# nRF24L01_Shield.net
KiCad netlist of a schematic drawn in EAGLE
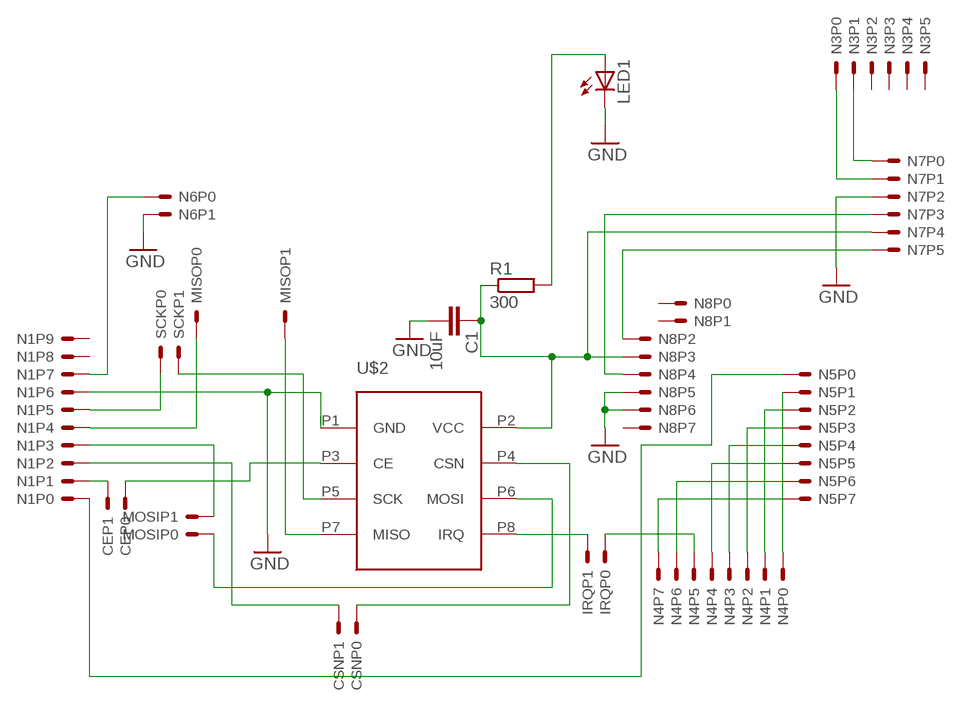
[diagram p0: schematic, sheet 1]

(export (version "E")
  (design (tool "Eeschema 10.0.6"))
  (components
    (comp (ref "C1")
      (value "10uF")
      (footprint "eagle-import:C2.5-4")
      (libsource (lib "eagle-import") (part "C2.5/4"))
    )
    (comp (ref "CE")
      (value "2PINHEADER")
      (footprint "eagle-import:2PINHEADER")
      (libsource (lib "eagle-import") (part "2PINHEADER"))
    )
    (comp (ref "CSN")
      (value "2PINHEADER")
      (footprint "eagle-import:2PINHEADER")
      (libsource (lib "eagle-import") (part "2PINHEADER"))
    )
    (comp (ref "IRQ")
      (value "2PINHEADER")
      (footprint "eagle-import:2PINHEADER")
      (libsource (lib "eagle-import") (part "2PINHEADER"))
    )
    (comp (ref "LED1")
      (value "LED3MM")
      (footprint "eagle-import:LED3MM")
      (libsource (lib "eagle-import") (part "LED3MM"))
    )
    (comp (ref "MISO")
      (value "2PINHEADER")
      (footprint "eagle-import:2PINHEADER")
      (libsource (lib "eagle-import") (part "2PINHEADER"))
    )
    (comp (ref "MOSI")
      (value "2PINHEADER")
      (footprint "eagle-import:2PINHEADER")
      (libsource (lib "eagle-import") (part "2PINHEADER"))
    )
    (comp (ref "N1")
      (value "10PINHEADER")
      (footprint "eagle-import:10PINHEADER")
      (libsource (lib "eagle-import") (part "10PINHEADER"))
    )
    (comp (ref "N3")
      (value "6PINHEADER")
      (footprint "eagle-import:6PINHEADER")
      (libsource (lib "eagle-import") (part "6PINHEADER"))
    )
    (comp (ref "N4")
      (value "8PINHEADER")
      (footprint "eagle-import:8PINHEADER")
      (libsource (lib "eagle-import") (part "nRF24L01_plus_8PINHEADER"))
    )
    (comp (ref "N5")
      (value "8PINHEADER")
      (footprint "eagle-import:8PINHEADER")
      (libsource (lib "eagle-import") (part "nRF24L01_plus_8PINHEADER"))
    )
    (comp (ref "N6")
      (value "2PINHEADER")
      (footprint "eagle-import:2PINHEADER")
      (libsource (lib "eagle-import") (part "2PINHEADER"))
    )
    (comp (ref "N7")
      (value "6PINHEADER")
      (footprint "eagle-import:6PINHEADER")
      (libsource (lib "eagle-import") (part "6PINHEADER"))
    )
    (comp (ref "N8")
      (value "8PINHEADER")
      (footprint "eagle-import:8PINHEADER")
      (libsource (lib "eagle-import") (part "8PINHEADER"))
    )
    (comp (ref "R1")
      (value "300")
      (footprint "eagle-import:0207_10")
      (libsource (lib "eagle-import") (part "R-EU_0207/10"))
    )
    (comp (ref "SCK")
      (value "2PINHEADER")
      (footprint "eagle-import:2PINHEADER")
      (libsource (lib "eagle-import") (part "2PINHEADER"))
    )
    (comp (ref "U$2")
      (value "NRF24L01A")
      (footprint "eagle-import:NRF24L01")
      (libsource (lib "eagle-import") (part "NRF24L01A"))
    )
  )
  (nets
    (net (code "1") (name "GND") (class "Default")
      (node (ref "C1") (pin "2") (pinfunction "2_2") (pintype "passive"))
      (node (ref "LED1") (pin "K") (pinfunction "C_K") (pintype "passive"))
      (node (ref "N1") (pin "P6") (pinfunction "S_P6") (pintype "passive"))
      (node (ref "N6") (pin "P1") (pinfunction "S_P1") (pintype "passive"))
      (node (ref "N7") (pin "P2") (pinfunction "S_P2") (pintype "passive"))
      (node (ref "N8") (pin "P5") (pinfunction "S_P5") (pintype "passive"))
      (node (ref "N8") (pin "P6") (pinfunction "S_P6") (pintype "passive"))
      (node (ref "U$2") (pin "P1") (pinfunction "GND_P1") (pintype "input"))
    )
    (net (code "2") (name "Net-(CEA-S)") (class "Default")
      (node (ref "CE") (pin "P0") (pinfunction "S_P0") (pintype "passive"))
      (node (ref "U$2") (pin "P3") (pinfunction "CE_P3") (pintype "bidirectional"))
    )
    (net (code "3") (name "Net-(CEB-S)") (class "Default")
      (node (ref "CE") (pin "P1") (pinfunction "S_P1") (pintype "passive"))
      (node (ref "N1") (pin "P1") (pinfunction "S_P1") (pintype "passive"))
    )
    (net (code "4") (name "Net-(CSNA-S)") (class "Default")
      (node (ref "CSN") (pin "P0") (pinfunction "S_P0") (pintype "passive"))
      (node (ref "U$2") (pin "P4") (pinfunction "CSN_P4") (pintype "bidirectional"))
    )
    (net (code "5") (name "Net-(CSNB-S)") (class "Default")
      (node (ref "CSN") (pin "P1") (pinfunction "S_P1") (pintype "passive"))
      (node (ref "N1") (pin "P2") (pinfunction "S_P2") (pintype "passive"))
    )
    (net (code "6") (name "Net-(IRQA-S)") (class "Default")
      (node (ref "IRQ") (pin "P0") (pinfunction "S_P0") (pintype "passive"))
      (node (ref "N4") (pin "P5") (pinfunction "S_P5") (pintype "passive"))
    )
    (net (code "7") (name "Net-(IRQB-S)") (class "Default")
      (node (ref "IRQ") (pin "P1") (pinfunction "S_P1") (pintype "passive"))
      (node (ref "U$2") (pin "P8") (pinfunction "IRQ_P8") (pintype "bidirectional"))
    )
    (net (code "8") (name "Net-(LED1-PadA)") (class "Default")
      (node (ref "LED1") (pin "A") (pinfunction "A_A") (pintype "passive"))
      (node (ref "R1") (pin "2") (pinfunction "2_2") (pintype "passive"))
    )
    (net (code "9") (name "Net-(MISOA-S)") (class "Default")
      (node (ref "MISO") (pin "P0") (pinfunction "S_P0") (pintype "passive"))
      (node (ref "N1") (pin "P4") (pinfunction "S_P4") (pintype "passive"))
    )
    (net (code "10") (name "Net-(MISOB-S)") (class "Default")
      (node (ref "MISO") (pin "P1") (pinfunction "S_P1") (pintype "passive"))
      (node (ref "U$2") (pin "P7") (pinfunction "MISO_P7") (pintype "bidirectional"))
    )
    (net (code "11") (name "Net-(MOSIA-S)") (class "Default")
      (node (ref "MOSI") (pin "P0") (pinfunction "S_P0") (pintype "passive"))
      (node (ref "U$2") (pin "P6") (pinfunction "MOSI_P6") (pintype "bidirectional"))
    )
    (net (code "12") (name "Net-(MOSIB-S)") (class "Default")
      (node (ref "MOSI") (pin "P1") (pinfunction "S_P1") (pintype "passive"))
      (node (ref "N1") (pin "P3") (pinfunction "S_P3") (pintype "passive"))
    )
    (net (code "13") (name "Net-(N1A-S)") (class "Default")
      (node (ref "N1") (pin "P0") (pinfunction "S_P0") (pintype "passive"))
      (node (ref "N5") (pin "P0") (pinfunction "S_P0") (pintype "passive"))
    )
    (net (code "14") (name "Net-(N1F-S)") (class "Default")
      (node (ref "N1") (pin "P5") (pinfunction "S_P5") (pintype "passive"))
      (node (ref "SCK") (pin "P0") (pinfunction "S_P0") (pintype "passive"))
    )
    (net (code "15") (name "Net-(N1H-S)") (class "Default")
      (node (ref "N1") (pin "P7") (pinfunction "S_P7") (pintype "passive"))
      (node (ref "N6") (pin "P0") (pinfunction "S_P0") (pintype "passive"))
    )
    (net (code "16") (name "Net-(N3A-S)") (class "Default")
      (node (ref "N3") (pin "P0") (pinfunction "S_P0") (pintype "passive"))
      (node (ref "N7") (pin "P1") (pinfunction "S_P1") (pintype "passive"))
    )
    (net (code "17") (name "Net-(N3B-S)") (class "Default")
      (node (ref "N3") (pin "P1") (pinfunction "S_P1") (pintype "passive"))
      (node (ref "N7") (pin "P0") (pinfunction "S_P0") (pintype "passive"))
    )
    (net (code "18") (name "Net-(N4A-S)") (class "Default")
      (node (ref "N4") (pin "P0") (pinfunction "S_P0") (pintype "passive"))
      (node (ref "N5") (pin "P1") (pinfunction "S_P1") (pintype "passive"))
    )
    (net (code "19") (name "Net-(N4B-S)") (class "Default")
      (node (ref "N4") (pin "P1") (pinfunction "S_P1") (pintype "passive"))
      (node (ref "N5") (pin "P2") (pinfunction "S_P2") (pintype "passive"))
    )
    (net (code "20") (name "Net-(N4C-S)") (class "Default")
      (node (ref "N4") (pin "P2") (pinfunction "S_P2") (pintype "passive"))
      (node (ref "N5") (pin "P3") (pinfunction "S_P3") (pintype "passive"))
    )
    (net (code "21") (name "Net-(N4D-S)") (class "Default")
      (node (ref "N4") (pin "P3") (pinfunction "S_P3") (pintype "passive"))
      (node (ref "N5") (pin "P4") (pinfunction "S_P4") (pintype "passive"))
    )
    (net (code "22") (name "Net-(N4E-S)") (class "Default")
      (node (ref "N4") (pin "P4") (pinfunction "S_P4") (pintype "passive"))
      (node (ref "N5") (pin "P5") (pinfunction "S_P5") (pintype "passive"))
    )
    (net (code "23") (name "Net-(N4G-S)") (class "Default")
      (node (ref "N4") (pin "P6") (pinfunction "S_P6") (pintype "passive"))
      (node (ref "N5") (pin "P6") (pinfunction "S_P6") (pintype "passive"))
    )
    (net (code "24") (name "Net-(N4H-S)") (class "Default")
      (node (ref "N4") (pin "P7") (pinfunction "S_P7") (pintype "passive"))
      (node (ref "N5") (pin "P7") (pinfunction "S_P7") (pintype "passive"))
    )
    (net (code "25") (name "Net-(N7D-S)") (class "Default")
      (node (ref "N7") (pin "P3") (pinfunction "S_P3") (pintype "passive"))
      (node (ref "N8") (pin "P4") (pinfunction "S_P4") (pintype "passive"))
    )
    (net (code "26") (name "Net-(N7E-S)") (class "Default")
      (node (ref "C1") (pin "1") (pinfunction "1_1") (pintype "passive"))
      (node (ref "N7") (pin "P4") (pinfunction "S_P4") (pintype "passive"))
      (node (ref "N8") (pin "P3") (pinfunction "S_P3") (pintype "passive"))
      (node (ref "R1") (pin "1") (pinfunction "1_1") (pintype "passive"))
      (node (ref "U$2") (pin "P2") (pinfunction "VCC_P2") (pintype "power_in"))
    )
    (net (code "27") (name "Net-(N7F-S)") (class "Default")
      (node (ref "N7") (pin "P5") (pinfunction "S_P5") (pintype "passive"))
      (node (ref "N8") (pin "P2") (pinfunction "S_P2") (pintype "passive"))
    )
    (net (code "28") (name "Net-(SCKB-S)") (class "Default")
      (node (ref "SCK") (pin "P1") (pinfunction "S_P1") (pintype "passive"))
      (node (ref "U$2") (pin "P5") (pinfunction "SCK_P5") (pintype "bidirectional"))
    )
    (net (code "29") (name "unconnected-(N1I-S-PadP8)") (class "Default")
      (node (ref "N1") (pin "P8") (pinfunction "S_P8") (pintype "passive"))
    )
    (net (code "30") (name "unconnected-(N1J-S-PadP9)") (class "Default")
      (node (ref "N1") (pin "P9") (pinfunction "S_P9") (pintype "passive"))
    )
    (net (code "31") (name "unconnected-(N3C-S-PadP2)") (class "Default")
      (node (ref "N3") (pin "P2") (pinfunction "S_P2") (pintype "passive"))
    )
    (net (code "32") (name "unconnected-(N3D-S-PadP3)") (class "Default")
      (node (ref "N3") (pin "P3") (pinfunction "S_P3") (pintype "passive"))
    )
    (net (code "33") (name "unconnected-(N3E-S-PadP4)") (class "Default")
      (node (ref "N3") (pin "P4") (pinfunction "S_P4") (pintype "passive"))
    )
    (net (code "34") (name "unconnected-(N3F-S-PadP5)") (class "Default")
      (node (ref "N3") (pin "P5") (pinfunction "S_P5") (pintype "passive"))
    )
    (net (code "35") (name "unconnected-(N8A-S-PadP0)") (class "Default")
      (node (ref "N8") (pin "P0") (pinfunction "S_P0") (pintype "passive"))
    )
    (net (code "36") (name "unconnected-(N8B-S-PadP1)") (class "Default")
      (node (ref "N8") (pin "P1") (pinfunction "S_P1") (pintype "passive"))
    )
    (net (code "37") (name "unconnected-(N8H-S-PadP7)") (class "Default")
      (node (ref "N8") (pin "P7") (pinfunction "S_P7") (pintype "passive"))
    )
  )
)
